# Tigershark_4DSystems_Display_Adapter.net
KiCad netlist of a schematic drawn in Altium Designer
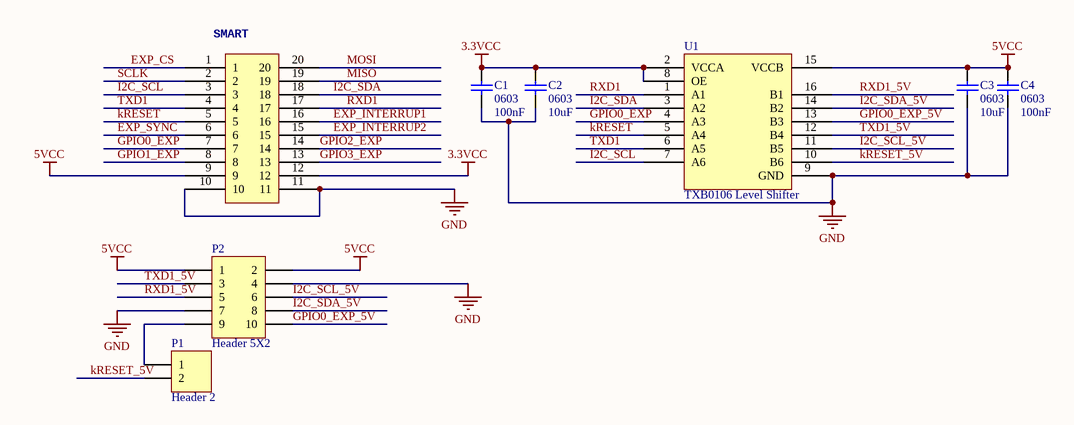
[diagram p0: Tigershark 4DSystems Display Adapter.SchDoc]

(export (version "E")
  (design (tool "Eeschema 10.0.6"))
  (components
    (comp (ref "C1")
      (value "0603")
      (footprint "1608[0603]")
      (description "Capacitor (Semiconductor SIM Model)")
      (fields (field (name "ALTIUM_VALUE") "100nF") (field (name "PUBLISHER") "Altium Limited"))
      (libsource (lib "Miscellaneous Devices") (part "Cap Semi"))
    )
    (comp (ref "C2")
      (value "0603")
      (footprint "1608[0603]")
      (description "Capacitor (Semiconductor SIM Model)")
      (fields (field (name "ALTIUM_VALUE") "10uF") (field (name "PUBLISHER") "Altium Limited"))
      (libsource (lib "Miscellaneous Devices") (part "Cap Semi"))
    )
    (comp (ref "C3")
      (value "0603")
      (footprint "1608[0603]")
      (description "Capacitor (Semiconductor SIM Model)")
      (fields (field (name "ALTIUM_VALUE") "10uF") (field (name "PUBLISHER") "Altium Limited"))
      (libsource (lib "Miscellaneous Devices") (part "Cap Semi"))
    )
    (comp (ref "C4")
      (value "0603")
      (footprint "1608[0603]")
      (description "Capacitor (Semiconductor SIM Model)")
      (fields (field (name "ALTIUM_VALUE") "100nF") (field (name "PUBLISHER") "Altium Limited"))
      (libsource (lib "Miscellaneous Devices") (part "Cap Semi"))
    )
    (comp (ref "P1")
      (value "Header 2")
      (footprint "HDR1X2")
      (description "Header, 2-Pin")
      (fields (field (name "PUBLISHER") "Altium Limited"))
      (libsource (lib "Miscellaneous Connectors") (part "Header 2"))
    )
    (comp (ref "P2")
      (value "Header 5X2")
      (footprint "HDR2X5")
      (description "Header, 5-Pin, Dual row")
      (fields (field (name "PUBLISHER") "Altium Limited"))
      (libsource (lib "Miscellaneous Connectors") (part "Header 5X2"))
    )
    (comp (ref "SMART")
      (value "10X2-0.1X0.05")
      (footprint "10X2-0.05X0.1 EXP")
      (fields (field (name "PUBLISHER") "UltiMachine"))
      (libsource (lib "TS4Dadapter Symbol Lib") (part "10X2-0.1X0.05"))
    )
    (comp (ref "U1")
      (value "TXB0106 Level Shifter")
      (footprint "TSOP65P640X120-16N")
      (description "TXB0106 - Bidriectional Opendrain/pushpull level shift")
      (libsource (lib "TS4Dadapter Symbol Lib") (part "TXB0106"))
    )
  )
  (nets
    (net (code "1") (name "/EXP_CS") (class "Default")
      (node (ref "SMART") (pin "1") (pinfunction "1_1") (pintype "passive"))
    )
    (net (code "2") (name "/EXP_INTERRUP1") (class "Default")
      (node (ref "SMART") (pin "16") (pinfunction "16_16") (pintype "passive"))
    )
    (net (code "3") (name "/EXP_INTERRUP2") (class "Default")
      (node (ref "SMART") (pin "15") (pinfunction "15_15") (pintype "passive"))
    )
    (net (code "4") (name "/EXP_SYNC") (class "Default")
      (node (ref "SMART") (pin "6") (pinfunction "6_6") (pintype "passive"))
    )
    (net (code "5") (name "/GPIO0_EXP") (class "Default")
      (node (ref "SMART") (pin "7") (pinfunction "7_7") (pintype "passive"))
      (node (ref "U1") (pin "4") (pinfunction "A3_4") (pintype "passive"))
    )
    (net (code "6") (name "/GPIO0_EXP_5V") (class "Default")
      (node (ref "P2") (pin "10") (pinfunction "10_10") (pintype "passive"))
      (node (ref "U1") (pin "13") (pinfunction "B3_13") (pintype "passive"))
    )
    (net (code "7") (name "/GPIO1_EXP") (class "Default")
      (node (ref "SMART") (pin "8") (pinfunction "8_8") (pintype "passive"))
    )
    (net (code "8") (name "/GPIO2_EXP") (class "Default")
      (node (ref "SMART") (pin "14") (pinfunction "14_14") (pintype "passive"))
    )
    (net (code "9") (name "/GPIO3_EXP") (class "Default")
      (node (ref "SMART") (pin "13") (pinfunction "13_13") (pintype "passive"))
    )
    (net (code "10") (name "/I2C_SCL") (class "Default")
      (node (ref "SMART") (pin "3") (pinfunction "3_3") (pintype "passive"))
      (node (ref "U1") (pin "7") (pinfunction "A6_7") (pintype "passive"))
    )
    (net (code "11") (name "/I2C_SCL_5V") (class "Default")
      (node (ref "P2") (pin "6") (pinfunction "6_6") (pintype "passive"))
      (node (ref "U1") (pin "11") (pinfunction "B5_11") (pintype "passive"))
    )
    (net (code "12") (name "/I2C_SDA") (class "Default")
      (node (ref "SMART") (pin "18") (pinfunction "18_18") (pintype "passive"))
      (node (ref "U1") (pin "3") (pinfunction "A2_3") (pintype "passive"))
    )
    (net (code "13") (name "/I2C_SDA_5V") (class "Default")
      (node (ref "P2") (pin "8") (pinfunction "8_8") (pintype "passive"))
      (node (ref "U1") (pin "14") (pinfunction "B2_14") (pintype "passive"))
    )
    (net (code "14") (name "/MISO") (class "Default")
      (node (ref "SMART") (pin "19") (pinfunction "19_19") (pintype "passive"))
    )
    (net (code "15") (name "/MOSI") (class "Default")
      (node (ref "SMART") (pin "20") (pinfunction "20_20") (pintype "passive"))
    )
    (net (code "16") (name "/RXD1") (class "Default")
      (node (ref "SMART") (pin "17") (pinfunction "17_17") (pintype "passive"))
      (node (ref "U1") (pin "1") (pinfunction "A1_1") (pintype "passive"))
    )
    (net (code "17") (name "/RXD1_5V") (class "Default")
      (node (ref "P2") (pin "5") (pinfunction "5_5") (pintype "passive"))
      (node (ref "U1") (pin "16") (pinfunction "B1_16") (pintype "passive"))
    )
    (net (code "18") (name "/SCLK") (class "Default")
      (node (ref "SMART") (pin "2") (pinfunction "2_2") (pintype "passive"))
    )
    (net (code "19") (name "/TXD1") (class "Default")
      (node (ref "SMART") (pin "4") (pinfunction "4_4") (pintype "passive"))
      (node (ref "U1") (pin "6") (pinfunction "A5_6") (pintype "passive"))
    )
    (net (code "20") (name "/TXD1_5V") (class "Default")
      (node (ref "P2") (pin "3") (pinfunction "3_3") (pintype "passive"))
      (node (ref "U1") (pin "12") (pinfunction "B4_12") (pintype "passive"))
    )
    (net (code "21") (name "/kRESET") (class "Default")
      (node (ref "SMART") (pin "5") (pinfunction "5_5") (pintype "passive"))
      (node (ref "U1") (pin "5") (pinfunction "A4_5") (pintype "passive"))
    )
    (net (code "22") (name "/kRESET_5V") (class "Default")
      (node (ref "P1") (pin "2") (pinfunction "2_2") (pintype "passive"))
      (node (ref "U1") (pin "10") (pinfunction "B6_10") (pintype "passive"))
    )
    (net (code "23") (name "3.3VCC") (class "Default")
      (node (ref "C1") (pin "2") (pinfunction "2_2") (pintype "passive"))
      (node (ref "C2") (pin "2") (pinfunction "2_2") (pintype "passive"))
      (node (ref "SMART") (pin "12") (pinfunction "12_12") (pintype "passive"))
      (node (ref "U1") (pin "2") (pinfunction "VCCA_2") (pintype "passive"))
      (node (ref "U1") (pin "8") (pinfunction "OE_8") (pintype "passive"))
    )
    (net (code "24") (name "5VCC") (class "Default")
      (node (ref "C3") (pin "2") (pinfunction "2_2") (pintype "passive"))
      (node (ref "C4") (pin "2") (pinfunction "2_2") (pintype "passive"))
      (node (ref "P2") (pin "1") (pinfunction "1_1") (pintype "passive"))
      (node (ref "P2") (pin "2") (pinfunction "2_2") (pintype "passive"))
      (node (ref "SMART") (pin "9") (pinfunction "9_9") (pintype "passive"))
      (node (ref "U1") (pin "15") (pinfunction "VCCB_15") (pintype "passive"))
    )
    (net (code "25") (name "GND") (class "Default")
      (node (ref "C1") (pin "1") (pinfunction "1_1") (pintype "passive"))
      (node (ref "C2") (pin "1") (pinfunction "1_1") (pintype "passive"))
      (node (ref "C3") (pin "1") (pinfunction "1_1") (pintype "passive"))
      (node (ref "C4") (pin "1") (pinfunction "1_1") (pintype "passive"))
      (node (ref "P2") (pin "4") (pinfunction "4_4") (pintype "passive"))
      (node (ref "P2") (pin "7") (pinfunction "7_7") (pintype "passive"))
      (node (ref "SMART") (pin "10") (pinfunction "10_10") (pintype "passive"))
      (node (ref "SMART") (pin "11") (pinfunction "11_11") (pintype "passive"))
      (node (ref "U1") (pin "9") (pinfunction "GND_9") (pintype "passive"))
    )
    (net (code "26") (name "Net-(P1-Pad1)") (class "Default")
      (node (ref "P1") (pin "1") (pinfunction "1_1") (pintype "passive"))
      (node (ref "P2") (pin "9") (pinfunction "9_9") (pintype "passive"))
    )
  )
)
